# Ammeter.net
KiCad netlist of a schematic drawn in EAGLE
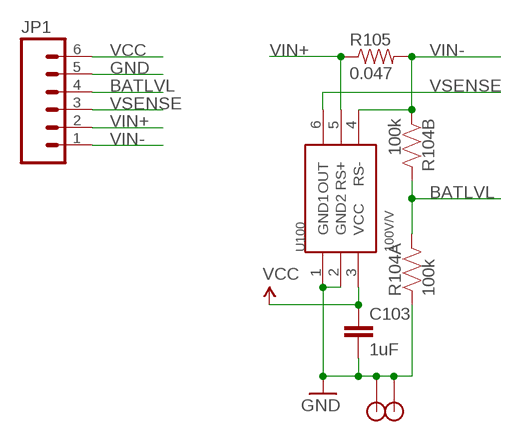
[diagram p0: schematic, sheet 1]

(export (version "E")
  (design (tool "Eeschema 10.0.6"))
  (components
    (comp (ref "C103")
      (value "1uF")
      (footprint "eagle-import:0402-CAP")
      (libsource (lib "eagle-import") (part "CAP0402-CAP"))
    )
    (comp (ref "JP1")
      (value "M06SIP")
      (footprint "eagle-import:1X06")
      (libsource (lib "eagle-import") (part "M06SIP"))
    )
    (comp (ref "R104")
      (value "100k")
      (footprint "eagle-import:CRA02")
      (libsource (lib "eagle-import") (part "RP2EXB24V"))
    )
    (comp (ref "R105")
      (value "0.047")
      (footprint "eagle-import:0402-RES")
      (libsource (lib "eagle-import") (part "RESISTOR0402-RES"))
    )
    (comp (ref "U$1")
      (value "STANDOFF")
      (footprint "eagle-import:STANDOFF")
      (libsource (lib "eagle-import") (part "STANDOFF"))
    )
    (comp (ref "U$2")
      (value "STANDOFF")
      (footprint "eagle-import:STANDOFF")
      (libsource (lib "eagle-import") (part "STANDOFF"))
    )
    (comp (ref "U100")
      (value "100V/V")
      (footprint "eagle-import:SOT-23-6")
      (libsource (lib "eagle-import") (part "MAX4173"))
    )
  )
  (nets
    (net (code "1") (name "/BATLVL") (class "Default")
      (node (ref "JP1") (pin "4") (pinfunction "4_4") (pintype "passive"))
      (node (ref "R104") (pin "3") (pinfunction "2_3") (pintype "passive"))
      (node (ref "R104") (pin "4") (pinfunction "2_4") (pintype "passive"))
    )
    (net (code "2") (name "/VIN+") (class "Default")
      (node (ref "JP1") (pin "2") (pinfunction "2_2") (pintype "passive"))
      (node (ref "R105") (pin "1") (pinfunction "1_1") (pintype "passive"))
      (node (ref "U100") (pin "5") (pinfunction "RS+_5") (pintype "bidirectional"))
    )
    (net (code "3") (name "/VIN-") (class "Default")
      (node (ref "JP1") (pin "1") (pinfunction "1_1") (pintype "passive"))
      (node (ref "R104") (pin "2") (pinfunction "1_2") (pintype "passive"))
      (node (ref "R105") (pin "2") (pinfunction "2_2") (pintype "passive"))
      (node (ref "U100") (pin "4") (pinfunction "RS-_4") (pintype "bidirectional"))
    )
    (net (code "4") (name "/VSENSE") (class "Default")
      (node (ref "JP1") (pin "3") (pinfunction "3_3") (pintype "passive"))
      (node (ref "U100") (pin "6") (pinfunction "OUT_6") (pintype "bidirectional"))
    )
    (net (code "5") (name "GND") (class "Default")
      (node (ref "C103") (pin "2") (pinfunction "2_2") (pintype "passive"))
      (node (ref "JP1") (pin "5") (pinfunction "5_5") (pintype "passive"))
      (node (ref "R104") (pin "1") (pinfunction "1_1") (pintype "passive"))
      (node (ref "U$1") (pin "P$1") (pinfunction "P$1_P$1") (pintype "bidirectional"))
      (node (ref "U$2") (pin "P$1") (pinfunction "P$1_P$1") (pintype "bidirectional"))
      (node (ref "U100") (pin "1") (pinfunction "GND1_1") (pintype "bidirectional"))
      (node (ref "U100") (pin "2") (pinfunction "GND2_2") (pintype "bidirectional"))
    )
    (net (code "6") (name "VCC") (class "Default")
      (node (ref "C103") (pin "1") (pinfunction "1_1") (pintype "passive"))
      (node (ref "JP1") (pin "6") (pinfunction "6_6") (pintype "passive"))
      (node (ref "U100") (pin "3") (pinfunction "VCC_3") (pintype "bidirectional"))
    )
  )
)
